# InterfaceBoard.net
KiCad netlist of a schematic drawn in Altium Designer
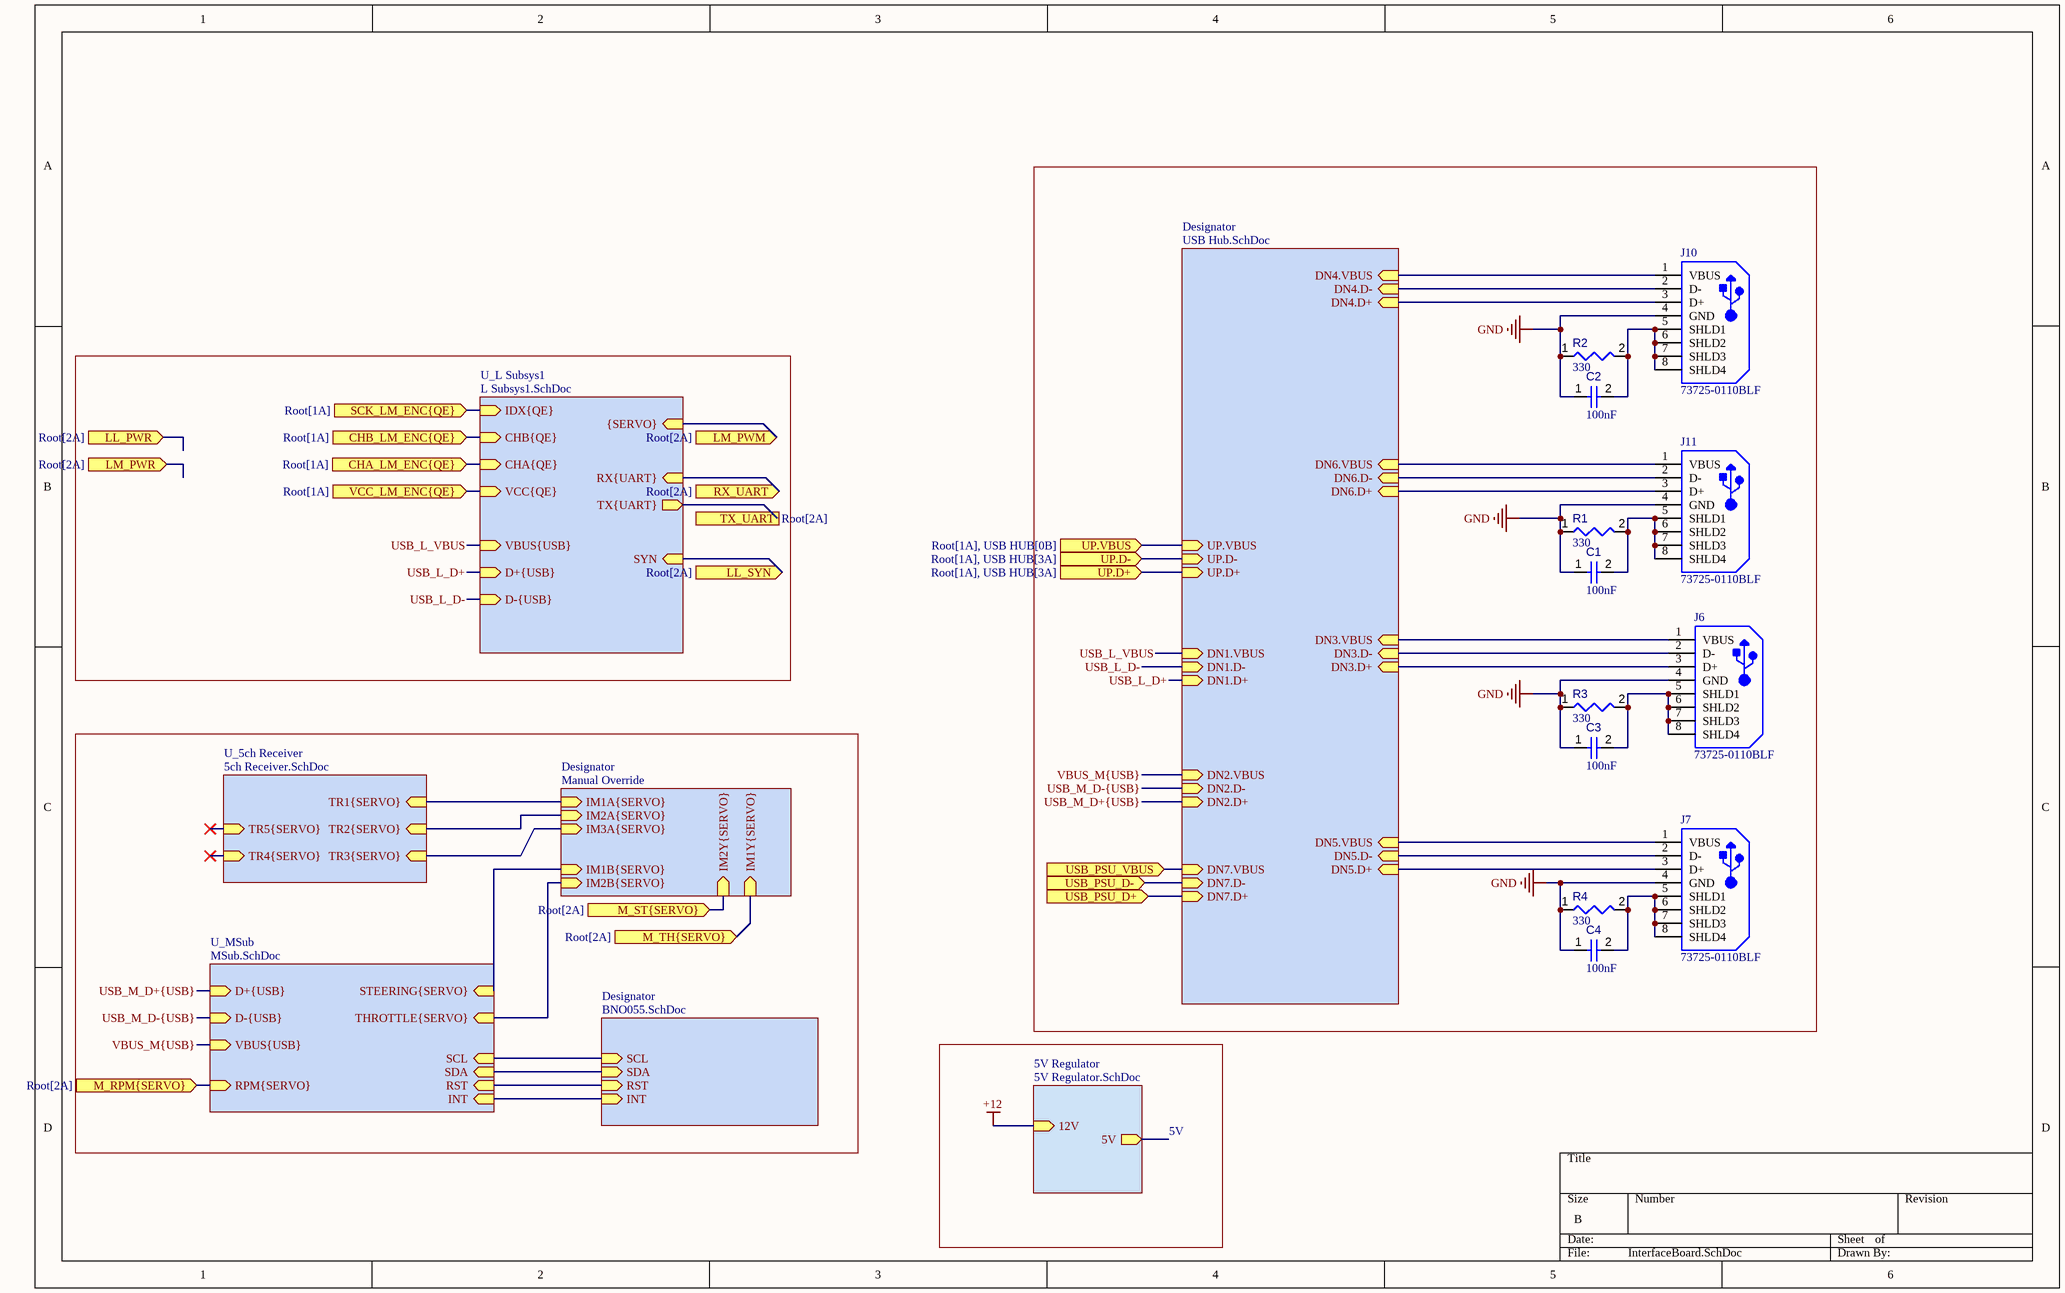
[diagram p0: InterfaceBoard.SchDoc]

(export (version "E")
  (design (tool "Eeschema 10.0.6"))
  (components
    (comp (ref "C1")
      (value "100nF")
      (footprint "CAPC1005X56X25LL10T15")
      (description "Chip Capacitor, 0.1 uF, +/- 5%, 16 V, 0402 (1005 Metric)")
      (fields (field (name "TOLERANCE") "5%") (field (name "Comment") "Capacitor 0.1 uF +/- 5% 16 V 0402"))
      (libsource (lib "Isaac Lee Altium Cloud") (part "CAP-NP-2"))
    )
    (comp (ref "C2")
      (value "100nF")
      (footprint "CAPC1005X56X25LL10T15")
      (description "Chip Capacitor, 0.1 uF, +/- 5%, 16 V, 0402 (1005 Metric)")
      (fields (field (name "TOLERANCE") "5%") (field (name "Comment") "Capacitor 0.1 uF +/- 5% 16 V 0402"))
      (libsource (lib "Isaac Lee Altium Cloud") (part "CAP-NP-2"))
    )
    (comp (ref "C3")
      (value "100nF")
      (footprint "CAPC1005X56X25LL10T15")
      (description "Chip Capacitor, 0.1 uF, +/- 5%, 16 V, 0402 (1005 Metric)")
      (fields (field (name "TOLERANCE") "5%") (field (name "Comment") "Capacitor 0.1 uF +/- 5% 16 V 0402"))
      (libsource (lib "Isaac Lee Altium Cloud") (part "CAP-NP-2"))
    )
    (comp (ref "C4")
      (value "100nF")
      (footprint "CAPC1005X56X25LL10T15")
      (description "Chip Capacitor, 0.1 uF, +/- 5%, 16 V, 0402 (1005 Metric)")
      (fields (field (name "TOLERANCE") "5%") (field (name "Comment") "Capacitor 0.1 uF +/- 5% 16 V 0402"))
      (libsource (lib "Isaac Lee Altium Cloud") (part "CAP-NP-2"))
    )
    (comp (ref "J6")
      (value "73725-0110BLF")
      (footprint "FCI-73725-0110BLF_V")
      (description "USB-A 2.0 Receptacle Connector, RA, -40 to 85 degC, 4-Pin THD, RoHS, Tube")
      (fields (field (name "MANUFACTURER") "FCI"))
      (libsource (lib "Altium Content Vault") (part "USB-4-4SHLD"))
    )
    (comp (ref "J7")
      (value "73725-0110BLF")
      (footprint "FCI-73725-0110BLF_V")
      (description "USB-A 2.0 Receptacle Connector, RA, -40 to 85 degC, 4-Pin THD, RoHS, Tube")
      (fields (field (name "MANUFACTURER") "FCI"))
      (libsource (lib "Altium Content Vault") (part "USB-4-4SHLD"))
    )
    (comp (ref "J10")
      (value "73725-0110BLF")
      (footprint "FCI-73725-0110BLF_V")
      (description "USB-A 2.0 Receptacle Connector, RA, -40 to 85 degC, 4-Pin THD, RoHS, Tube")
      (fields (field (name "MANUFACTURER") "FCI"))
      (libsource (lib "Altium Content Vault") (part "USB-4-4SHLD"))
    )
    (comp (ref "J11")
      (value "73725-0110BLF")
      (footprint "FCI-73725-0110BLF_V")
      (description "USB-A 2.0 Receptacle Connector, RA, -40 to 85 degC, 4-Pin THD, RoHS, Tube")
      (fields (field (name "MANUFACTURER") "FCI"))
      (libsource (lib "Altium Content Vault") (part "USB-4-4SHLD"))
    )
    (comp (ref "R1")
      (value "330")
      (footprint "RESC0402(1005)_L")
      (description "Chip Resistor, 330 Ohms, +/-5 %, 63 mW, -55 to 155 degC, 0402")
      (fields (field (name "POWER") "63mW") (field (name "TOLERANCE") "5%"))
      (libsource (lib "Isaac Lee Altium Cloud") (part "RES-2"))
    )
    (comp (ref "R2")
      (value "330")
      (footprint "RESC0402(1005)_L")
      (description "Chip Resistor, 330 Ohms, +/-5 %, 63 mW, -55 to 155 degC, 0402")
      (fields (field (name "POWER") "63mW") (field (name "TOLERANCE") "5%"))
      (libsource (lib "Isaac Lee Altium Cloud") (part "RES-2"))
    )
    (comp (ref "R3")
      (value "330")
      (footprint "RESC0402(1005)_L")
      (description "Chip Resistor, 330 Ohms, +/-5 %, 63 mW, -55 to 155 degC, 0402")
      (fields (field (name "POWER") "63mW") (field (name "TOLERANCE") "5%"))
      (libsource (lib "Isaac Lee Altium Cloud") (part "RES-2"))
    )
    (comp (ref "R4")
      (value "330")
      (footprint "RESC0402(1005)_L")
      (description "Chip Resistor, 330 Ohms, +/-5 %, 63 mW, -55 to 155 degC, 0402")
      (fields (field (name "POWER") "63mW") (field (name "TOLERANCE") "5%"))
      (libsource (lib "Isaac Lee Altium Cloud") (part "RES-2"))
    )
  )
  (nets
    (net (code "15") (name "/DN3.D+") (class "Default")
      (node (ref "J6") (pin "3") (pinfunction "D+_3") (pintype "passive"))
    )
    (net (code "16") (name "/DN3.D-") (class "Default")
      (node (ref "J6") (pin "2") (pinfunction "D-_2") (pintype "passive"))
    )
    (net (code "17") (name "/DN3.VBUS") (class "Default")
      (node (ref "J6") (pin "1") (pinfunction "VBUS_1") (pintype "passive"))
    )
    (net (code "18") (name "/DN4.D+") (class "Default")
      (node (ref "J10") (pin "3") (pinfunction "D+_3") (pintype "passive"))
    )
    (net (code "19") (name "/DN4.D-") (class "Default")
      (node (ref "J10") (pin "2") (pinfunction "D-_2") (pintype "passive"))
    )
    (net (code "20") (name "/DN4.VBUS") (class "Default")
      (node (ref "J10") (pin "1") (pinfunction "VBUS_1") (pintype "passive"))
    )
    (net (code "21") (name "/DN5.D+") (class "Default")
      (node (ref "J7") (pin "3") (pinfunction "D+_3") (pintype "passive"))
    )
    (net (code "22") (name "/DN5.D-") (class "Default")
      (node (ref "J7") (pin "2") (pinfunction "D-_2") (pintype "passive"))
    )
    (net (code "23") (name "/DN5.VBUS") (class "Default")
      (node (ref "J7") (pin "1") (pinfunction "VBUS_1") (pintype "passive"))
    )
    (net (code "24") (name "/DN6.D+") (class "Default")
      (node (ref "J11") (pin "3") (pinfunction "D+_3") (pintype "passive"))
    )
    (net (code "25") (name "/DN6.D-") (class "Default")
      (node (ref "J11") (pin "2") (pinfunction "D-_2") (pintype "passive"))
    )
    (net (code "26") (name "/DN6.VBUS") (class "Default")
      (node (ref "J11") (pin "1") (pinfunction "VBUS_1") (pintype "passive"))
    )
    (net (code "62") (name "GND") (class "Default")
      (node (ref "C1") (pin "1") (pinfunction "1_1") (pintype "passive"))
      (node (ref "C2") (pin "1") (pinfunction "1_1") (pintype "passive"))
      (node (ref "C3") (pin "1") (pinfunction "1_1") (pintype "passive"))
      (node (ref "C4") (pin "1") (pinfunction "1_1") (pintype "passive"))
      (node (ref "J10") (pin "4") (pinfunction "GND_4") (pintype "passive"))
      (node (ref "J11") (pin "4") (pinfunction "GND_4") (pintype "passive"))
      (node (ref "J6") (pin "4") (pinfunction "GND_4") (pintype "passive"))
      (node (ref "J7") (pin "4") (pinfunction "GND_4") (pintype "passive"))
      (node (ref "R1") (pin "1") (pinfunction "1_1") (pintype "passive"))
      (node (ref "R2") (pin "1") (pinfunction "1_1") (pintype "passive"))
      (node (ref "R3") (pin "1") (pinfunction "1_1") (pintype "passive"))
      (node (ref "R4") (pin "1") (pinfunction "1_1") (pintype "passive"))
    )
    (net (code "63") (name "Net-(J6-SHLD1)") (class "Default")
      (node (ref "C3") (pin "2") (pinfunction "2_2") (pintype "passive"))
      (node (ref "J6") (pin "5") (pinfunction "SHLD1_5") (pintype "passive"))
      (node (ref "J6") (pin "6") (pinfunction "SHLD2_6") (pintype "passive"))
      (node (ref "J6") (pin "7") (pinfunction "SHLD3_7") (pintype "passive"))
      (node (ref "J6") (pin "8") (pinfunction "SHLD4_8") (pintype "passive"))
      (node (ref "R3") (pin "2") (pinfunction "2_2") (pintype "passive"))
    )
    (net (code "64") (name "Net-(J7-SHLD1)") (class "Default")
      (node (ref "C4") (pin "2") (pinfunction "2_2") (pintype "passive"))
      (node (ref "J7") (pin "5") (pinfunction "SHLD1_5") (pintype "passive"))
      (node (ref "J7") (pin "6") (pinfunction "SHLD2_6") (pintype "passive"))
      (node (ref "J7") (pin "7") (pinfunction "SHLD3_7") (pintype "passive"))
      (node (ref "J7") (pin "8") (pinfunction "SHLD4_8") (pintype "passive"))
      (node (ref "R4") (pin "2") (pinfunction "2_2") (pintype "passive"))
    )
    (net (code "65") (name "Net-(J10-SHLD1)") (class "Default")
      (node (ref "C2") (pin "2") (pinfunction "2_2") (pintype "passive"))
      (node (ref "J10") (pin "5") (pinfunction "SHLD1_5") (pintype "passive"))
      (node (ref "J10") (pin "6") (pinfunction "SHLD2_6") (pintype "passive"))
      (node (ref "J10") (pin "7") (pinfunction "SHLD3_7") (pintype "passive"))
      (node (ref "J10") (pin "8") (pinfunction "SHLD4_8") (pintype "passive"))
      (node (ref "R2") (pin "2") (pinfunction "2_2") (pintype "passive"))
    )
    (net (code "66") (name "Net-(J11-SHLD1)") (class "Default")
      (node (ref "C1") (pin "2") (pinfunction "2_2") (pintype "passive"))
      (node (ref "J11") (pin "5") (pinfunction "SHLD1_5") (pintype "passive"))
      (node (ref "J11") (pin "6") (pinfunction "SHLD2_6") (pintype "passive"))
      (node (ref "J11") (pin "7") (pinfunction "SHLD3_7") (pintype "passive"))
      (node (ref "J11") (pin "8") (pinfunction "SHLD4_8") (pintype "passive"))
      (node (ref "R1") (pin "2") (pinfunction "2_2") (pintype "passive"))
    )
  )
)
